# podule_2040.net
KiCad netlist of a schematic drawn in EAGLE
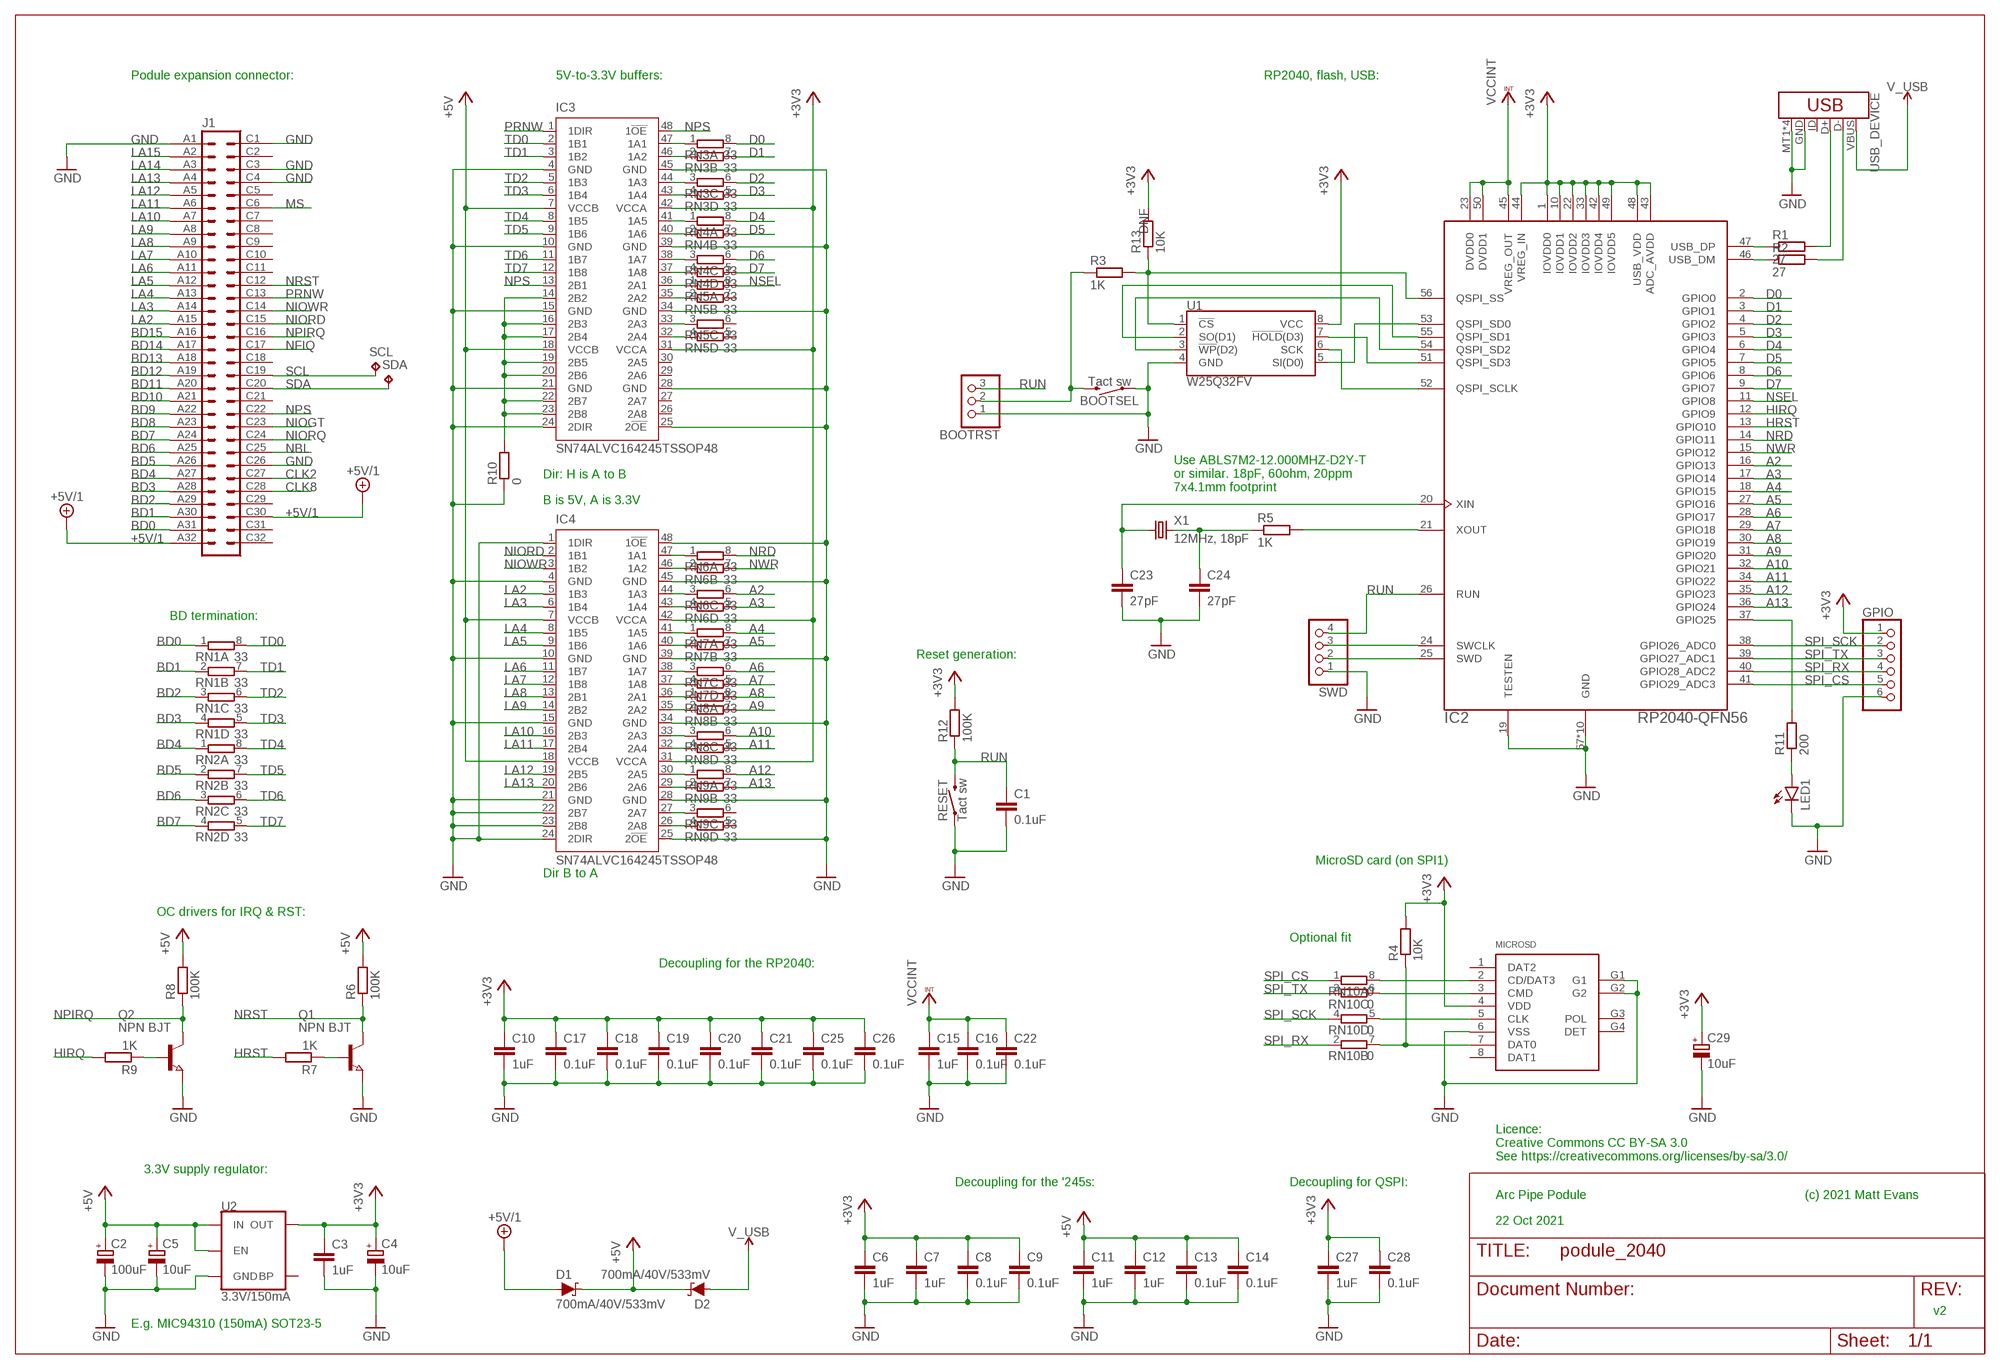
[diagram p0: schematic, sheet 1]

(export (version "E")
  (design (tool "Eeschema 10.0.6"))
  (components
    (comp (ref "BOOTRST")
      (value "PINHD-1X3")
      (footprint "eagle-import:1X03")
      (libsource (lib "eagle-import") (part "PINHD-1X3"))
    )
    (comp (ref "BOOTSEL")
      (value "Tact sw")
      (footprint "eagle-import:TACTILE_SWITCH_SMD_5.2MM")
      (libsource (lib "eagle-import") (part "MOMENTARY-SWITCH-SPST-SMD-5.2-REDUNDANT"))
    )
    (comp (ref "C1")
      (value "0.1uF")
      (footprint "eagle-import:C0603K")
      (libsource (lib "eagle-import") (part "C-EUC0603K"))
    )
    (comp (ref "C2")
      (value "100uF")
      (footprint "eagle-import:CT6032")
      (libsource (lib "eagle-import") (part "CPOL-EUCT6032"))
    )
    (comp (ref "C3")
      (value "1uF")
      (footprint "eagle-import:C0603K")
      (libsource (lib "eagle-import") (part "C-EUC0603K"))
    )
    (comp (ref "C4")
      (value "10uF")
      (footprint "eagle-import:A_3216-18W")
      (libsource (lib "eagle-import") (part "CPOL-EUA/3216-18W"))
    )
    (comp (ref "C5")
      (value "10uF")
      (footprint "eagle-import:A_3216-18W")
      (libsource (lib "eagle-import") (part "CPOL-EUA/3216-18W"))
    )
    (comp (ref "C6")
      (value "1uF")
      (footprint "eagle-import:C0603K")
      (libsource (lib "eagle-import") (part "C-EUC0603K"))
    )
    (comp (ref "C7")
      (value "1uF")
      (footprint "eagle-import:C0603K")
      (libsource (lib "eagle-import") (part "C-EUC0603K"))
    )
    (comp (ref "C8")
      (value "0.1uF")
      (footprint "eagle-import:C0603K")
      (libsource (lib "eagle-import") (part "C-EUC0603K"))
    )
    (comp (ref "C9")
      (value "0.1uF")
      (footprint "eagle-import:C0603K")
      (libsource (lib "eagle-import") (part "C-EUC0603K"))
    )
    (comp (ref "C10")
      (value "1uF")
      (footprint "eagle-import:C0603K")
      (libsource (lib "eagle-import") (part "C-EUC0603K"))
    )
    (comp (ref "C11")
      (value "1uF")
      (footprint "eagle-import:C0603K")
      (libsource (lib "eagle-import") (part "C-EUC0603K"))
    )
    (comp (ref "C12")
      (value "1uF")
      (footprint "eagle-import:C0603K")
      (libsource (lib "eagle-import") (part "C-EUC0603K"))
    )
    (comp (ref "C13")
      (value "0.1uF")
      (footprint "eagle-import:C0603K")
      (libsource (lib "eagle-import") (part "C-EUC0603K"))
    )
    (comp (ref "C14")
      (value "0.1uF")
      (footprint "eagle-import:C0603K")
      (libsource (lib "eagle-import") (part "C-EUC0603K"))
    )
    (comp (ref "C15")
      (value "1uF")
      (footprint "eagle-import:C0603K")
      (libsource (lib "eagle-import") (part "C-EUC0603K"))
    )
    (comp (ref "C16")
      (value "0.1uF")
      (footprint "eagle-import:C0603K")
      (libsource (lib "eagle-import") (part "C-EUC0603K"))
    )
    (comp (ref "C17")
      (value "0.1uF")
      (footprint "eagle-import:C0603K")
      (libsource (lib "eagle-import") (part "C-EUC0603K"))
    )
    (comp (ref "C18")
      (value "0.1uF")
      (footprint "eagle-import:C0603K")
      (libsource (lib "eagle-import") (part "C-EUC0603K"))
    )
    (comp (ref "C19")
      (value "0.1uF")
      (footprint "eagle-import:C0603K")
      (libsource (lib "eagle-import") (part "C-EUC0603K"))
    )
    (comp (ref "C20")
      (value "0.1uF")
      (footprint "eagle-import:C0603K")
      (libsource (lib "eagle-import") (part "C-EUC0603K"))
    )
    (comp (ref "C21")
      (value "0.1uF")
      (footprint "eagle-import:C0603K")
      (libsource (lib "eagle-import") (part "C-EUC0603K"))
    )
    (comp (ref "C22")
      (value "0.1uF")
      (footprint "eagle-import:C0603K")
      (libsource (lib "eagle-import") (part "C-EUC0603K"))
    )
    (comp (ref "C23")
      (value "27pF")
      (footprint "eagle-import:C0603K")
      (libsource (lib "eagle-import") (part "C-EUC0603K"))
    )
    (comp (ref "C24")
      (value "27pF")
      (footprint "eagle-import:C0603K")
      (libsource (lib "eagle-import") (part "C-EUC0603K"))
    )
    (comp (ref "C25")
      (value "0.1uF")
      (footprint "eagle-import:C0603K")
      (libsource (lib "eagle-import") (part "C-EUC0603K"))
    )
    (comp (ref "C26")
      (value "0.1uF")
      (footprint "eagle-import:C0603K")
      (libsource (lib "eagle-import") (part "C-EUC0603K"))
    )
    (comp (ref "C27")
      (value "1uF")
      (footprint "eagle-import:C0603K")
      (libsource (lib "eagle-import") (part "C-EUC0603K"))
    )
    (comp (ref "C28")
      (value "0.1uF")
      (footprint "eagle-import:C0603K")
      (libsource (lib "eagle-import") (part "C-EUC0603K"))
    )
    (comp (ref "C29")
      (value "10uF")
      (footprint "eagle-import:A_3216-18W")
      (libsource (lib "eagle-import") (part "CPOL-EUA/3216-18W"))
    )
    (comp (ref "D1")
      (value "700mA/40V/533mV")
      (footprint "eagle-import:SOT23-3")
      (libsource (lib "eagle-import") (part "DIODE-SCHOTTKY-ZLLS500"))
    )
    (comp (ref "D2")
      (value "700mA/40V/533mV")
      (footprint "eagle-import:SOT23-3")
      (libsource (lib "eagle-import") (part "DIODE-SCHOTTKY-ZLLS500"))
    )
    (comp (ref "GPIO")
      (value "PINHD-1X6")
      (footprint "eagle-import:1X06")
      (libsource (lib "eagle-import") (part "PINHD-1X6"))
    )
    (comp (ref "IC2")
      (value "RP2040-QFN56")
      (footprint "eagle-import:RP2040-QFN-56")
      (libsource (lib "eagle-import") (part "RP2040-QFN56"))
    )
    (comp (ref "IC3")
      (value "SN74ALVC164245TSSOP48")
      (footprint "eagle-import:TSSOP48")
      (libsource (lib "eagle-import") (part "SN74ALVC164245TSSOP48"))
    )
    (comp (ref "IC4")
      (value "SN74ALVC164245TSSOP48")
      (footprint "eagle-import:TSSOP48")
      (libsource (lib "eagle-import") (part "SN74ALVC164245TSSOP48"))
    )
    (comp (ref "J1")
      (value "VG64SHORT")
      (footprint "eagle-import:VG64KB-80MM")
      (libsource (lib "eagle-import") (part "VG64SHORT"))
    )
    (comp (ref "LED1")
      (value "LEDCHIPLED_1206")
      (footprint "eagle-import:CHIPLED_1206")
      (libsource (lib "eagle-import") (part "LEDCHIPLED_1206"))
    )
    (comp (ref "MICROSD")
      (value "MOLEX-USD-47309")
      (footprint "eagle-import:MOLEX-USD-47309")
      (libsource (lib "eagle-import") (part "MOLEX-USD-47309"))
    )
    (comp (ref "Q1")
      (value "NPN BJT")
      (footprint "eagle-import:SOT23")
      (libsource (lib "eagle-import") (part "NPN-TRANSISTOR_SOT23"))
    )
    (comp (ref "Q2")
      (value "NPN BJT")
      (footprint "eagle-import:SOT23")
      (libsource (lib "eagle-import") (part "NPN-TRANSISTOR_SOT23"))
    )
    (comp (ref "R1")
      (value "27")
      (footprint "eagle-import:R0805")
      (libsource (lib "eagle-import") (part "R-EU_R0805"))
    )
    (comp (ref "R2")
      (value "27")
      (footprint "eagle-import:R0805")
      (libsource (lib "eagle-import") (part "R-EU_R0805"))
    )
    (comp (ref "R3")
      (value "1K")
      (footprint "eagle-import:R0805")
      (libsource (lib "eagle-import") (part "R-EU_R0805"))
    )
    (comp (ref "R4")
      (value "10K")
      (footprint "eagle-import:R0805")
      (libsource (lib "eagle-import") (part "R-EU_R0805"))
    )
    (comp (ref "R5")
      (value "1K")
      (footprint "eagle-import:R0805")
      (libsource (lib "eagle-import") (part "R-EU_R0805"))
    )
    (comp (ref "R6")
      (value "100K")
      (footprint "eagle-import:R0805")
      (libsource (lib "eagle-import") (part "R-EU_R0805"))
    )
    (comp (ref "R7")
      (value "1K")
      (footprint "eagle-import:R0805")
      (libsource (lib "eagle-import") (part "R-EU_R0805"))
    )
    (comp (ref "R8")
      (value "100K")
      (footprint "eagle-import:R0805")
      (libsource (lib "eagle-import") (part "R-EU_R0805"))
    )
    (comp (ref "R9")
      (value "1K")
      (footprint "eagle-import:R0805")
      (libsource (lib "eagle-import") (part "R-EU_R0805"))
    )
    (comp (ref "R10")
      (value "0")
      (footprint "eagle-import:R0603")
      (libsource (lib "eagle-import") (part "R-EU_R0603"))
    )
    (comp (ref "R11")
      (value "200")
      (footprint "eagle-import:R0805")
      (libsource (lib "eagle-import") (part "R-EU_R0805"))
    )
    (comp (ref "R12")
      (value "100K")
      (footprint "eagle-import:R0805")
      (libsource (lib "eagle-import") (part "R-EU_R0805"))
    )
    (comp (ref "R13")
      (value "10K")
      (footprint "eagle-import:R0805")
      (libsource (lib "eagle-import") (part "R-EU_R0805"))
    )
    (comp (ref "RESET")
      (value "Tact sw")
      (footprint "eagle-import:TACTILE_SWITCH_SMD_5.2MM")
      (libsource (lib "eagle-import") (part "MOMENTARY-SWITCH-SPST-SMD-5.2-REDUNDANT"))
    )
    (comp (ref "RN1")
      (value "33")
      (footprint "eagle-import:0603-ARC")
      (libsource (lib "eagle-import") (part "4R-N0603-ARC"))
    )
    (comp (ref "RN2")
      (value "33")
      (footprint "eagle-import:0603-ARC")
      (libsource (lib "eagle-import") (part "4R-N0603-ARC"))
    )
    (comp (ref "RN3")
      (value "33")
      (footprint "eagle-import:0603-ARC")
      (libsource (lib "eagle-import") (part "4R-N0603-ARC"))
    )
    (comp (ref "RN4")
      (value "33")
      (footprint "eagle-import:0603-ARC")
      (libsource (lib "eagle-import") (part "4R-N0603-ARC"))
    )
    (comp (ref "RN5")
      (value "33")
      (footprint "eagle-import:0603-ARC")
      (libsource (lib "eagle-import") (part "4R-N0603-ARC"))
    )
    (comp (ref "RN6")
      (value "33")
      (footprint "eagle-import:0603-ARC")
      (libsource (lib "eagle-import") (part "4R-N0603-ARC"))
    )
    (comp (ref "RN7")
      (value "33")
      (footprint "eagle-import:0603-ARC")
      (libsource (lib "eagle-import") (part "4R-N0603-ARC"))
    )
    (comp (ref "RN8")
      (value "33")
      (footprint "eagle-import:0603-ARC")
      (libsource (lib "eagle-import") (part "4R-N0603-ARC"))
    )
    (comp (ref "RN9")
      (value "33")
      (footprint "eagle-import:0603-ARC")
      (libsource (lib "eagle-import") (part "4R-N0603-ARC"))
    )
    (comp (ref "RN10")
      (value "0")
      (footprint "eagle-import:0603-ARC")
      (libsource (lib "eagle-import") (part "4R-N0603-ARC"))
    )
    (comp (ref "SCL")
      (value "TPTP15R")
      (footprint "eagle-import:TP15R")
      (libsource (lib "eagle-import") (part "TPTP15R"))
    )
    (comp (ref "SDA")
      (value "TPTP15R")
      (footprint "eagle-import:TP15R")
      (libsource (lib "eagle-import") (part "TPTP15R"))
    )
    (comp (ref "SWD")
      (value "PINHD-1X4")
      (footprint "eagle-import:1X04")
      (libsource (lib "eagle-import") (part "PINHD-1X4"))
    )
    (comp (ref "U1")
      (value "W25Q32FV")
      (footprint "eagle-import:SOIC-8")
      (libsource (lib "eagle-import") (part "W25Q32FVSS"))
    )
    (comp (ref "U2")
      (value "3.3V/150mA")
      (footprint "eagle-import:SOT23-5")
      (libsource (lib "eagle-import") (part "V_REG_MIC52053.3V"))
    )
    (comp (ref "USB_DEVICE")
      (value "USB_MICRO-B_SMT")
      (footprint "eagle-import:USB-MICROB")
      (libsource (lib "eagle-import") (part "USB_MICRO-B_SMT"))
    )
    (comp (ref "X1")
      (value "12MHz, 18pF")
      (footprint "eagle-import:7.5X5-2-PAD")
      (libsource (lib "eagle-import") (part "CRYSTALS-NOGND-12SMX-A"))
    )
  )
  (nets
    (net (code "1") (name "+3V3") (class "Default")
      (node (ref "C10") (pin "1") (pinfunction "1_1") (pintype "passive"))
      (node (ref "C17") (pin "1") (pinfunction "1_1") (pintype "passive"))
      (node (ref "C18") (pin "1") (pinfunction "1_1") (pintype "passive"))
      (node (ref "C19") (pin "1") (pinfunction "1_1") (pintype "passive"))
      (node (ref "C20") (pin "1") (pinfunction "1_1") (pintype "passive"))
      (node (ref "C21") (pin "1") (pinfunction "1_1") (pintype "passive"))
      (node (ref "C25") (pin "1") (pinfunction "1_1") (pintype "passive"))
      (node (ref "C26") (pin "1") (pinfunction "1_1") (pintype "passive"))
      (node (ref "C27") (pin "1") (pinfunction "1_1") (pintype "passive"))
      (node (ref "C28") (pin "1") (pinfunction "1_1") (pintype "passive"))
      (node (ref "C29") (pin "+") (pinfunction "+_+") (pintype "passive"))
      (node (ref "C3") (pin "1") (pinfunction "1_1") (pintype "passive"))
      (node (ref "C4") (pin "+") (pinfunction "+_+") (pintype "passive"))
      (node (ref "C6") (pin "1") (pinfunction "1_1") (pintype "passive"))
      (node (ref "C7") (pin "1") (pinfunction "1_1") (pintype "passive"))
      (node (ref "C8") (pin "1") (pinfunction "1_1") (pintype "passive"))
      (node (ref "C9") (pin "1") (pinfunction "1_1") (pintype "passive"))
      (node (ref "GPIO") (pin "1") (pinfunction "1_1") (pintype "passive"))
      (node (ref "IC2") (pin "1") (pinfunction "IOVDD0_1") (pintype "power_in"))
      (node (ref "IC2") (pin "10") (pinfunction "IOVDD1_10") (pintype "power_in"))
      (node (ref "IC2") (pin "22") (pinfunction "IOVDD2_22") (pintype "power_in"))
      (node (ref "IC2") (pin "33") (pinfunction "IOVDD3_33") (pintype "power_in"))
      (node (ref "IC2") (pin "42") (pinfunction "IOVDD4_42") (pintype "power_in"))
      (node (ref "IC2") (pin "43") (pinfunction "ADC_AVDD_43") (pintype "power_in"))
      (node (ref "IC2") (pin "44") (pinfunction "VREG_IN_44") (pintype "power_in"))
      (node (ref "IC2") (pin "48") (pinfunction "USB_VDD_48") (pintype "power_in"))
      (node (ref "IC2") (pin "49") (pinfunction "IOVDD5_49") (pintype "power_in"))
      (node (ref "IC3") (pin "31") (pinfunction "VCCA_31") (pintype "power_in"))
      (node (ref "IC3") (pin "42") (pinfunction "VCCA_42") (pintype "power_in"))
      (node (ref "IC4") (pin "31") (pinfunction "VCCA_31") (pintype "power_in"))
      (node (ref "IC4") (pin "42") (pinfunction "VCCA_42") (pintype "power_in"))
      (node (ref "MICROSD") (pin "4") (pinfunction "VDD_4") (pintype "bidirectional"))
      (node (ref "R12") (pin "2") (pinfunction "2_2") (pintype "passive"))
      (node (ref "R13") (pin "2") (pinfunction "2_2") (pintype "passive"))
      (node (ref "R4") (pin "2") (pinfunction "2_2") (pintype "passive"))
      (node (ref "U1") (pin "8") (pinfunction "VCC_8") (pintype "bidirectional"))
      (node (ref "U2") (pin "5") (pinfunction "OUT_5") (pintype "passive"))
    )
    (net (code "2") (name "+5V") (class "Default")
      (node (ref "C11") (pin "1") (pinfunction "1_1") (pintype "passive"))
      (node (ref "C12") (pin "1") (pinfunction "1_1") (pintype "passive"))
      (node (ref "C13") (pin "1") (pinfunction "1_1") (pintype "passive"))
      (node (ref "C14") (pin "1") (pinfunction "1_1") (pintype "passive"))
      (node (ref "C2") (pin "+") (pinfunction "+_+") (pintype "passive"))
      (node (ref "C5") (pin "+") (pinfunction "+_+") (pintype "passive"))
      (node (ref "D1") (pin "3") (pinfunction "C_3") (pintype "passive"))
      (node (ref "D2") (pin "3") (pinfunction "C_3") (pintype "passive"))
      (node (ref "IC3") (pin "18") (pinfunction "VCCB_18") (pintype "power_in"))
      (node (ref "IC3") (pin "7") (pinfunction "VCCB_7") (pintype "power_in"))
      (node (ref "IC4") (pin "18") (pinfunction "VCCB_18") (pintype "power_in"))
      (node (ref "IC4") (pin "7") (pinfunction "VCCB_7") (pintype "power_in"))
      (node (ref "R6") (pin "2") (pinfunction "2_2") (pintype "passive"))
      (node (ref "R8") (pin "2") (pinfunction "2_2") (pintype "passive"))
      (node (ref "U2") (pin "1") (pinfunction "IN_1") (pintype "input"))
      (node (ref "U2") (pin "3") (pinfunction "EN_3") (pintype "input"))
    )
    (net (code "3") (name "+5V{slash}1") (class "Default")
      (node (ref "D1") (pin "1") (pinfunction "A_1") (pintype "passive"))
      (node (ref "J1") (pin "A32") (pinfunction "A32_A32") (pintype "passive"))
      (node (ref "J1") (pin "C30") (pinfunction "C30_C30") (pintype "passive"))
    )
    (net (code "4") (name "/A2") (class "Default")
      (node (ref "IC2") (pin "16") (pinfunction "GPIO13_16") (pintype "bidirectional"))
      (node (ref "RN6") (pin "6") (pinfunction "2_6") (pintype "passive"))
    )
    (net (code "5") (name "/A3") (class "Default")
      (node (ref "IC2") (pin "17") (pinfunction "GPIO14_17") (pintype "bidirectional"))
      (node (ref "RN6") (pin "5") (pinfunction "2_5") (pintype "passive"))
    )
    (net (code "6") (name "/A4") (class "Default")
      (node (ref "IC2") (pin "18") (pinfunction "GPIO15_18") (pintype "bidirectional"))
      (node (ref "RN7") (pin "8") (pinfunction "2_8") (pintype "passive"))
    )
    (net (code "7") (name "/A5") (class "Default")
      (node (ref "IC2") (pin "27") (pinfunction "GPIO16_27") (pintype "bidirectional"))
      (node (ref "RN7") (pin "7") (pinfunction "2_7") (pintype "passive"))
    )
    (net (code "8") (name "/A6") (class "Default")
      (node (ref "IC2") (pin "28") (pinfunction "GPIO17_28") (pintype "bidirectional"))
      (node (ref "RN7") (pin "6") (pinfunction "2_6") (pintype "passive"))
    )
    (net (code "9") (name "/A7") (class "Default")
      (node (ref "IC2") (pin "29") (pinfunction "GPIO18_29") (pintype "bidirectional"))
      (node (ref "RN7") (pin "5") (pinfunction "2_5") (pintype "passive"))
    )
    (net (code "10") (name "/A8") (class "Default")
      (node (ref "IC2") (pin "30") (pinfunction "GPIO19_30") (pintype "bidirectional"))
      (node (ref "RN8") (pin "8") (pinfunction "2_8") (pintype "passive"))
    )
    (net (code "11") (name "/A9") (class "Default")
      (node (ref "IC2") (pin "31") (pinfunction "GPIO20_31") (pintype "bidirectional"))
      (node (ref "RN8") (pin "7") (pinfunction "2_7") (pintype "passive"))
    )
    (net (code "12") (name "/A10") (class "Default")
      (node (ref "IC2") (pin "32") (pinfunction "GPIO21_32") (pintype "bidirectional"))
      (node (ref "RN8") (pin "6") (pinfunction "2_6") (pintype "passive"))
    )
    (net (code "13") (name "/A11") (class "Default")
      (node (ref "IC2") (pin "34") (pinfunction "GPIO22_34") (pintype "bidirectional"))
      (node (ref "RN8") (pin "5") (pinfunction "2_5") (pintype "passive"))
    )
    (net (code "14") (name "/A12") (class "Default")
      (node (ref "IC2") (pin "35") (pinfunction "GPIO23_35") (pintype "bidirectional"))
      (node (ref "RN9") (pin "8") (pinfunction "2_8") (pintype "passive"))
    )
    (net (code "15") (name "/A13") (class "Default")
      (node (ref "IC2") (pin "36") (pinfunction "GPIO24_36") (pintype "bidirectional"))
      (node (ref "RN9") (pin "7") (pinfunction "2_7") (pintype "passive"))
    )
    (net (code "16") (name "/BD0") (class "Default")
      (node (ref "J1") (pin "A31") (pinfunction "A31_A31") (pintype "passive"))
      (node (ref "RN1") (pin "1") (pinfunction "1_1") (pintype "passive"))
    )
    (net (code "17") (name "/BD1") (class "Default")
      (node (ref "J1") (pin "A30") (pinfunction "A30_A30") (pintype "passive"))
      (node (ref "RN1") (pin "2") (pinfunction "1_2") (pintype "passive"))
    )
    (net (code "18") (name "/BD2") (class "Default")
      (node (ref "J1") (pin "A29") (pinfunction "A29_A29") (pintype "passive"))
      (node (ref "RN1") (pin "3") (pinfunction "1_3") (pintype "passive"))
    )
    (net (code "19") (name "/BD3") (class "Default")
      (node (ref "J1") (pin "A28") (pinfunction "A28_A28") (pintype "passive"))
      (node (ref "RN1") (pin "4") (pinfunction "1_4") (pintype "passive"))
    )
    (net (code "20") (name "/BD4") (class "Default")
      (node (ref "J1") (pin "A27") (pinfunction "A27_A27") (pintype "passive"))
      (node (ref "RN2") (pin "1") (pinfunction "1_1") (pintype "passive"))
    )
    (net (code "21") (name "/BD5") (class "Default")
      (node (ref "J1") (pin "A26") (pinfunction "A26_A26") (pintype "passive"))
      (node (ref "RN2") (pin "2") (pinfunction "1_2") (pintype "passive"))
    )
    (net (code "22") (name "/BD6") (class "Default")
      (node (ref "J1") (pin "A25") (pinfunction "A25_A25") (pintype "passive"))
      (node (ref "RN2") (pin "3") (pinfunction "1_3") (pintype "passive"))
    )
    (net (code "23") (name "/BD7") (class "Default")
      (node (ref "J1") (pin "A24") (pinfunction "A24_A24") (pintype "passive"))
      (node (ref "RN2") (pin "4") (pinfunction "1_4") (pintype "passive"))
    )
    (net (code "24") (name "/BD8") (class "Default")
      (node (ref "J1") (pin "A23") (pinfunction "A23_A23") (pintype "passive"))
    )
    (net (code "25") (name "/BD9") (class "Default")
      (node (ref "J1") (pin "A22") (pinfunction "A22_A22") (pintype "passive"))
    )
    (net (code "26") (name "/BD10") (class "Default")
      (node (ref "J1") (pin "A21") (pinfunction "A21_A21") (pintype "passive"))
    )
    (net (code "27") (name "/BD11") (class "Default")
      (node (ref "J1") (pin "A20") (pinfunction "A20_A20") (pintype "passive"))
    )
    (net (code "28") (name "/BD12") (class "Default")
      (node (ref "J1") (pin "A19") (pinfunction "A19_A19") (pintype "passive"))
    )
    (net (code "29") (name "/BD13") (class "Default")
      (node (ref "J1") (pin "A18") (pinfunction "A18_A18") (pintype "passive"))
    )
    (net (code "30") (name "/BD14") (class "Default")
      (node (ref "J1") (pin "A17") (pinfunction "A17_A17") (pintype "passive"))
    )
    (net (code "31") (name "/BD15") (class "Default")
      (node (ref "J1") (pin "A16") (pinfunction "A16_A16") (pintype "passive"))
    )
    (net (code "32") (name "/CLK2") (class "Default")
      (node (ref "J1") (pin "C27") (pinfunction "C27_C27") (pintype "passive"))
    )
    (net (code "33") (name "/CLK8") (class "Default")
      (node (ref "J1") (pin "C28") (pinfunction "C28_C28") (pintype "passive"))
    )
    (net (code "34") (name "/D0") (class "Default")
      (node (ref "IC2") (pin "2") (pinfunction "GPIO0_2") (pintype "bidirectional"))
      (node (ref "RN3") (pin "8") (pinfunction "2_8") (pintype "passive"))
    )
    (net (code "35") (name "/D1") (class "Default")
      (node (ref "IC2") (pin "3") (pinfunction "GPIO1_3") (pintype "bidirectional"))
      (node (ref "RN3") (pin "7") (pinfunction "2_7") (pintype "passive"))
    )
    (net (code "36") (name "/D2") (class "Default")
      (node (ref "IC2") (pin "4") (pinfunction "GPIO2_4") (pintype "bidirectional"))
      (node (ref "RN3") (pin "6") (pinfunction "2_6") (pintype "passive"))
    )
    (net (code "37") (name "/D3") (class "Default")
      (node (ref "IC2") (pin "5") (pinfunction "GPIO3_5") (pintype "bidirectional"))
      (node (ref "RN3") (pin "5") (pinfunction "2_5") (pintype "passive"))
    )
    (net (code "38") (name "/D4") (class "Default")
      (node (ref "IC2") (pin "6") (pinfunction "GPIO4_6") (pintype "bidirectional"))
      (node (ref "RN4") (pin "8") (pinfunction "2_8") (pintype "passive"))
    )
    (net (code "39") (name "/D5") (class "Default")
      (node (ref "IC2") (pin "7") (pinfunction "GPIO5_7") (pintype "bidirectional"))
      (node (ref "RN4") (pin "7") (pinfunction "2_7") (pintype "passive"))
    )
    (net (code "40") (name "/D6") (class "Default")
      (node (ref "IC2") (pin "8") (pinfunction "GPIO6_8") (pintype "bidirectional"))
      (node (ref "RN4") (pin "6") (pinfunction "2_6") (pintype "passive"))
    )
    (net (code "41") (name "/D7") (class "Default")
      (node (ref "IC2") (pin "9") (pinfunction "GPIO7_9") (pintype "bidirectional"))
      (node (ref "RN4") (pin "5") (pinfunction "2_5") (pintype "passive"))
    )
    (net (code "42") (name "/HIRQ") (class "Default")
      (node (ref "IC2") (pin "12") (pinfunction "GPIO9_12") (pintype "bidirectional"))
      (node (ref "R9") (pin "2") (pinfunction "2_2") (pintype "passive"))
    )
    (net (code "43") (name "/HRST") (class "Default")
      (node (ref "IC2") (pin "13") (pinfunction "GPIO10_13") (pintype "bidirectional"))
      (node (ref "R7") (pin "2") (pinfunction "2_2") (pintype "passive"))
    )
    (net (code "44") (name "/LA2") (class "Default")
      (node (ref "IC4") (pin "5") (pinfunction "1B3_5") (pintype "tri_state"))
      (node (ref "J1") (pin "A15") (pinfunction "A15_A15") (pintype "passive"))
    )
    (net (code "45") (name "/LA3") (class "Default")
      (node (ref "IC4") (pin "6") (pinfunction "1B4_6") (pintype "tri_state"))
      (node (ref "J1") (pin "A14") (pinfunction "A14_A14") (pintype "passive"))
    )
    (net (code "46") (name "/LA4") (class "Default")
      (node (ref "IC4") (pin "8") (pinfunction "1B5_8") (pintype "tri_state"))
      (node (ref "J1") (pin "A13") (pinfunction "A13_A13") (pintype "passive"))
    )
    (net (code "47") (name "/LA5") (class "Default")
      (node (ref "IC4") (pin "9") (pinfunction "1B6_9") (pintype "tri_state"))
      (node (ref "J1") (pin "A12") (pinfunction "A12_A12") (pintype "passive"))
    )
    (net (code "48") (name "/LA6") (class "Default")
      (node (ref "IC4") (pin "11") (pinfunction "1B7_11") (pintype "tri_state"))
      (node (ref "J1") (pin "A11") (pinfunction "A11_A11") (pintype "passive"))
    )
    (net (code "49") (name "/LA7") (class "Default")
      (node (ref "IC4") (pin "12") (pinfunction "1B8_12") (pintype "tri_state"))
      (node (ref "J1") (pin "A10") (pinfunction "A10_A10") (pintype "passive"))
    )
    (net (code "50") (name "/LA8") (class "Default")
      (node (ref "IC4") (pin "13") (pinfunction "2B1_13") (pintype "tri_state"))
      (node (ref "J1") (pin "A9") (pinfunction "A9_A9") (pintype "passive"))
    )
    (net (code "51") (name "/LA9") (class "Default")
      (node (ref "IC4") (pin "14") (pinfunction "2B2_14") (pintype "tri_state"))
      (node (ref "J1") (pin "A8") (pinfunction "A8_A8") (pintype "passive"))
    )
    (net (code "52") (name "/LA10") (class "Default")
      (node (ref "IC4") (pin "16") (pinfunction "2B3_16") (pintype "tri_state"))
      (node (ref "J1") (pin "A7") (pinfunction "A7_A7") (pintype "passive"))
    )
    (net (code "53") (name "/LA11") (class "Default")
      (node (ref "IC4") (pin "17") (pinfunction "2B4_17") (pintype "tri_state"))
      (node (ref "J1") (pin "A6") (pinfunction "A6_A6") (pintype "passive"))
    )
    (net (code "54") (name "/LA12") (class "Default")
      (node (ref "IC4") (pin "19") (pinfunction "2B5_19") (pintype "tri_state"))
      (node (ref "J1") (pin "A5") (pinfunction "A5_A5") (pintype "passive"))
    )
    (net (code "55") (name "/LA13") (class "Default")
      (node (ref "IC4") (pin "20") (pinfunction "2B6_20") (pintype "tri_state"))
      (node (ref "J1") (pin "A4") (pinfunction "A4_A4") (pintype "passive"))
    )
    (net (code "56") (name "/LA14") (class "Default")
      (node (ref "J1") (pin "A3") (pinfunction "A3_A3") (pintype "passive"))
    )
    (net (code "57") (name "/LA15") (class "Default")
      (node (ref "J1") (pin "A2") (pinfunction "A2_A2") (pintype "passive"))
    )
    (net (code "58") (name "/MS") (class "Default")
      (node (ref "J1") (pin "C6") (pinfunction "C6_C6") (pintype "passive"))
    )
    (net (code "59") (name "/NBL") (class "Default")
      (node (ref "J1") (pin "C25") (pinfunction "C25_C25") (pintype "passive"))
    )
    (net (code "60") (name "/NFIQ") (class "Default")
      (node (ref "J1") (pin "C17") (pinfunction "C17_C17") (pintype "passive"))
    )
    (net (code "61") (name "/NIOGT") (class "Default")
      (node (ref "J1") (pin "C23") (pinfunction "C23_C23") (pintype "passive"))
    )
    (net (code "62") (name "/NIORD") (class "Default")
      (node (ref "IC4") (pin "2") (pinfunction "1B1_2") (pintype "tri_state"))
      (node (ref "J1") (pin "C15") (pinfunction "C15_C15") (pintype "passive"))
    )
    (net (code "63") (name "/NIORQ") (class "Default")
      (node (ref "J1") (pin "C24") (pinfunction "C24_C24") (pintype "passive"))
    )
    (net (code "64") (name "/NIOWR") (class "Default")
      (node (ref "IC4") (pin "3") (pinfunction "1B2_3") (pintype "tri_state"))
      (node (ref "J1") (pin "C14") (pinfunction "C14_C14") (pintype "passive"))
    )
    (net (code "65") (name "/NPIRQ") (class "Default")
      (node (ref "J1") (pin "C16") (pinfunction "C16_C16") (pintype "passive"))
      (node (ref "Q2") (pin "3") (pinfunction "C_3") (pintype "passive"))
      (node (ref "R8") (pin "1") (pinfunction "1_1") (pintype "passive"))
    )
    (net (code "66") (name "/NPS") (class "Default")
      (node (ref "IC3") (pin "13") (pinfunction "2B1_13") (pintype "tri_state"))
      (node (ref "IC3") (pin "48") (pinfunction "1~{OE}_48") (pintype "input"))
      (node (ref "J1") (pin "C22") (pinfunction "C22_C22") (pintype "passive"))
    )
    (net (code "67") (name "/NRD") (class "Default")
      (node (ref "IC2") (pin "14") (pinfunction "GPIO11_14") (pintype "bidirectional"))
      (node (ref "RN6") (pin "8") (pinfunction "2_8") (pintype "passive"))
    )
    (net (code "68") (name "/NRST") (class "Default")
      (node (ref "J1") (pin "C12") (pinfunction "C12_C12") (pintype "passive"))
      (node (ref "Q1") (pin "3") (pinfunction "C_3") (pintype "passive"))
      (node (ref "R6") (pin "1") (pinfunction "1_1") (pintype "passive"))
    )
    (net (code "69") (name "/NSEL") (class "Default")
      (node (ref "IC2") (pin "11") (pinfunction "GPIO8_11") (pintype "bidirectional"))
      (node (ref "RN5") (pin "8") (pinfunction "2_8") (pintype "passive"))
    )
    (net (code "70") (name "/NWR") (class "Default")
      (node (ref "IC2") (pin "15") (pinfunction "GPIO12_15") (pintype "bidirectional"))
      (node (ref "RN6") (pin "7") (pinfunction "2_7") (pintype "passive"))
    )
    (net (code "71") (name "/PRNW") (class "Default")
      (node (ref "IC3") (pin "1") (pinfunction "1DIR_1") (pintype "input"))
      (node (ref "J1") (pin "C13") (pinfunction "C13_C13") (pintype "passive"))
    )
    (net (code "72") (name "/RUN") (class "Default")
      (node (ref "BOOTRST") (pin "3") (pinfunction "3_3") (pintype "passive"))
      (node (ref "C1") (pin "1") (pinfunction "1_1") (pintype "passive"))
      (node (ref "IC2") (pin "26") (pinfunction "RUN_26") (pintype "input"))
      (node (ref "R12") (pin "1") (pinfunction "1_1") (pintype "passive"))
      (node (ref "RESET") (pin "3") (pinfunction "2_3") (pintype "passive"))
      (node (ref "RESET") (pin "4") (pinfunction "2_4") (pintype "passive"))
      (node (ref "SWD") (pin "4") (pinfunction "4_4") (pintype "passive"))
    )
    (net (code "73") (name "/SCL") (class "Default")
      (node (ref "J1") (pin "C19") (pinfunction "C19_C19") (pintype "passive"))
      (node (ref "SCL") (pin "TP") (pinfunction "TP_TP") (pintype "input"))
    )
    (net (code "74") (name "/SDA") (class "Default")
      (node (ref "J1") (pin "C20") (pinfunction "C20_C20") (pintype "passive"))
      (node (ref "SDA") (pin "TP") (pinfunction "TP_TP") (pintype "input"))
    )
    (net (code "75") (name "/SPI_CS") (class "Default")
      (node (ref "GPIO") (pin "5") (pinfunction "5_5") (pintype "passive"))
      (node (ref "IC2") (pin "41") (pinfunction "GPIO29_ADC3_41") (pintype "bidirectional"))
      (node (ref "RN10") (pin "1") (pinfunction "1_1") (pintype "passive"))
    )
    (net (code "76") (name "/SPI_RX") (class "Default")
      (node (ref "GPIO") (pin "4") (pinfunction "4_4") (pintype "passive"))
      (node (ref "IC2") (pin "40") (pinfunction "GPIO28_ADC2_40") (pintype "bidirectional"))
      (node (ref "RN10") (pin "2") (pinfunction "1_2") (pintype "passive"))
    )
    (net (code "77") (name "/SPI_SCK") (class "Default")
      (node (ref "GPIO") (pin "2") (pinfunction "2_2") (pintype "passive"))
      (node (ref "IC2") (pin "38") (pinfunction "GPIO26_ADC0_38") (pintype "bidirectional"))
      (node (ref "RN10") (pin "4") (pinfunction "1_4") (pintype "passive"))
    )
    (net (code "78") (name "/SPI_TX") (class "Default")
      (node (ref "GPIO") (pin "3") (pinfunction "3_3") (pintype "passive"))
      (node (ref "IC2") (pin "39") (pinfunction "GPIO27_ADC1_39") (pintype "bidirectional"))
      (node (ref "RN10") (pin "3") (pinfunction "1_3") (pintype "passive"))
    )
    (net (code "79") (name "/TD0") (class "Default")
      (node (ref "IC3") (pin "2") (pinfunction "1B1_2") (pintype "tri_state"))
      (node (ref "RN1") (pin "8") (pinfunction "2_8") (pintype "passive"))
    )
    (net (code "80") (name "/TD1") (class "Default")
      (node (ref "IC3") (pin "3") (pinfunction "1B2_3") (pintype "tri_state"))
      (node (ref "RN1") (pin "7") (pinfunction "2_7") (pintype "passive"))
    )
    (net (code "81") (name "/TD2") (class "Default")
      (node (ref "IC3") (pin "5") (pinfunction "1B3_5") (pintype "tri_state"))
      (node (ref "RN1") (pin "6") (pinfunction "2_6") (pintype "passive"))
    )
    (net (code "82") (name "/TD3") (class "Default")
      (node (ref "IC3") (pin "6") (pinfunction "1B4_6") (pintype "tri_state"))
      (node (ref "RN1") (pin "5") (pinfunction "2_5") (pintype "passive"))
    )
    (net (code "83") (name "/TD4") (class "Default")
      (node (ref "IC3") (pin "8") (pinfunction "1B5_8") (pintype "tri_state"))
      (node (ref "RN2") (pin "8") (pinfunction "2_8") (pintype "passive"))
    )
    (net (code "84") (name "/TD5") (class "Default")
      (node (ref "IC3") (pin "9") (pinfunction "1B6_9") (pintype "tri_state"))
      (node (ref "RN2") (pin "7") (pinfunction "2_7") (pintype "passive"))
    )
    (net (code "85") (name "/TD6") (class "Default")
      (node (ref "IC3") (pin "11") (pinfunction "1B7_11") (pintype "tri_state"))
      (node (ref "RN2") (pin "6") (pinfunction "2_6") (pintype "passive"))
    )
    (net (code "86") (name "/TD7") (class "Default")
      (node (ref "IC3") (pin "12") (pinfunction "1B8_12") (pintype "tri_state"))
      (node (ref "RN2") (pin "5") (pinfunction "2_5") (pintype "passive"))
    )
    (net (code "87") (name "GND") (class "Default")
      (node (ref "BOOTRST") (pin "1") (pinfunction "1_1") (pintype "passive"))
      (node (ref "BOOTSEL") (pin "1") (pinfunction "1_1") (pintype "passive"))
      (node (ref "BOOTSEL") (pin "2") (pinfunction "1_2") (pintype "passive"))
      (node (ref "C1") (pin "2") (pinfunction "2_2") (pintype "passive"))
      (node (ref "C10") (pin "2") (pinfunction "2_2") (pintype "passive"))
      (node (ref "C11") (pin "2") (pinfunction "2_2") (pintype "passive"))
      (node (ref "C12") (pin "2") (pinfunction "2_2") (pintype "passive"))
      (node (ref "C13") (pin "2") (pinfunction "2_2") (pintype "passive"))
      (node (ref "C14") (pin "2") (pinfunction "2_2") (pintype "passive"))
      (node (ref "C15") (pin "2") (pinfunction "2_2") (pintype "passive"))
      (node (ref "C16") (pin "2") (pinfunction "2_2") (pintype "passive"))
      (node (ref "C17") (pin "2") (pinfunction "2_2") (pintype "passive"))
      (node (ref "C18") (pin "2") (pinfunction "2_2") (pintype "passive"))
      (node (ref "C19") (pin "2") (pinfunction "2_2") (pintype "passive"))
      (node (ref "C2") (pin "-") (pinfunction "-_-") (pintype "passive"))
      (node (ref "C20") (pin "2") (pinfunction "2_2") (pintype "passive"))
      (node (ref "C21") (pin "2") (pinfunction "2_2") (pintype "passive"))
      (node (ref "C22") (pin "2") (pinfunction "2_2") (pintype "passive"))
      (node (ref "C23") (pin "2") (pinfunction "2_2") (pintype "passive"))
      (node (ref "C24") (pin "2") (pinfunction "2_2") (pintype "passive"))
      (node (ref "C25") (pin "2") (pinfunction "2_2") (pintype "passive"))
      (node (ref "C26") (pin "2") (pinfunction "2_2") (pintype "passive"))
      (node (ref "C27") (pin "2") (pinfunction "2_2") (pintype "passive"))
      (node (ref "C28") (pin "2") (pinfunction "2_2") (pintype "passive"))
      (node (ref "C29") (pin "-") (pinfunction "-_-") (pintype "passive"))
      (node (ref "C3") (pin "2") (pinfunction "2_2") (pintype "passive"))
      (node (ref "C4") (pin "-") (pinfunction "-_-") (pintype "passive"))
      (node (ref "C5") (pin "-") (pinfunction "-_-") (pintype "passive"))
      (node (ref "C6") (pin "2") (pinfunction "2_2") (pintype "passive"))
      (node (ref "C7") (pin "2") (pinfunction "2_2") (pintype "passive"))
      (node (ref "C8") (pin "2") (pinfunction "2_2") (pintype "passive"))
      (node (ref "C9") (pin "2") (pinfunction "2_2") (pintype "passive"))
      (node (ref "GPIO") (pin "6") (pinfunction "6_6") (pintype "passive"))
      (node (ref "IC2") (pin "19") (pinfunction "TESTEN_19") (pintype "passive"))
      (node (ref "IC2") (pin "57") (pinfunction "GND_57") (pintype "power_in"))
      (node (ref "IC2") (pin "58") (pinfunction "GND_58") (pintype "power_in"))
      (node (ref "IC2") (pin "59") (pinfunction "GND_59") (pintype "power_in"))
      (node (ref "IC2") (pin "60") (pinfunction "GND_60") (pintype "power_in"))
      (node (ref "IC2") (pin "61") (pinfunction "GND_61") (pintype "power_in"))
      (node (ref "IC2") (pin "62") (pinfunction "GND_62") (pintype "power_in"))
      (node (ref "IC2") (pin "63") (pinfunction "GND_63") (pintype "power_in"))
      (node (ref "IC2") (pin "64") (pinfunction "GND_64") (pintype "power_in"))
      (node (ref "IC2") (pin "65") (pinfunction "GND_65") (pintype "power_in"))
      (node (ref "IC2") (pin "66") (pinfunction "GND_66") (pintype "power_in"))
      (node (ref "IC3") (pin "10") (pinfunction "GND_10") (pintype "power_in"))
      (node (ref "IC3") (pin "15") (pinfunction "GND_15") (pintype "power_in"))
      (node (ref "IC3") (pin "21") (pinfunction "GND_21") (pintype "tri_state"))
      (node (ref "IC3") (pin "24") (pinfunction "2DIR_24") (pintype "input"))
      (node (ref "IC3") (pin "25") (pinfunction "2~{OE}_25") (pintype "input"))
      (node (ref "IC3") (pin "28") (pinfunction "GND_28") (pintype "power_in"))
      (node (ref "IC3") (pin "34") (pinfunction "GND_34") (pintype "power_in"))
      (node (ref "IC3") (pin "39") (pinfunction "GND_39") (pintype "tri_state"))
      (node (ref "IC3") (pin "4") (pinfunction "GND_4") (pintype "power_in"))
      (node (ref "IC3") (pin "45") (pinfunction "GND_45") (pintype "power_in"))
      (node (ref "IC4") (pin "1") (pinfunction "1DIR_1") (pintype "input"))
      (node (ref "IC4") (pin "10") (pinfunction "GND_10") (pintype "power_in"))
      (node (ref "IC4") (pin "15") (pinfunction "GND_15") (pintype "power_in"))
      (node (ref "IC4") (pin "21") (pinfunction "GND_21") (pintype "tri_state"))
      (node (ref "IC4") (pin "22") (pinfunction "2B7_22") (pintype "tri_state"))
      (node (ref "IC4") (pin "23") (pinfunction "2B8_23") (pintype "tri_state"))
      (node (ref "IC4") (pin "24") (pinfunction "2DIR_24") (pintype "input"))
      (node (ref "IC4") (pin "25") (pinfunction "2~{OE}_25") (pintype "input"))
      (node (ref "IC4") (pin "28") (pinfunction "GND_28") (pintype "power_in"))
      (node (ref "IC4") (pin "34") (pinfunction "GND_34") (pintype "power_in"))
      (node (ref "IC4") (pin "39") (pinfunction "GND_39") (pintype "tri_state"))
      (node (ref "IC4") (pin "4") (pinfunction "GND_4") (pintype "power_in"))
      (node (ref "IC4") (pin "45") (pinfunction "GND_45") (pintype "power_in"))
      (node (ref "IC4") (pin "48") (pinfunction "1~{OE}_48") (pintype "input"))
      (node (ref "J1") (pin "A1") (pinfunction "A1_A1") (pintype "passive"))
      (node (ref "J1") (pin "C1") (pinfunction "C1_C1") (pintype "passive"))
      (node (ref "J1") (pin "C26") (pinfunction "C26_C26") (pintype "passive"))
      (node (ref "J1") (pin "C3") (pinfunction "C3_C3") (pintype "passive"))
      (node (ref "J1") (pin "C4") (pinfunction "C4_C4") (pintype "passive"))
      (node (ref "LED1") (pin "C") (pinfunction "C_C") (pintype "passive"))
      (node (ref "MICROSD") (pin "6") (pinfunction "VSS_6") (pintype "bidirectional"))
      (node (ref "MICROSD") (pin "G1") (pinfunction "G1_G1") (pintype "bidirectional"))
      (node (ref "MICROSD") (pin "G2") (pinfunction "G2_G2") (pintype "bidirectional"))
      (node (ref "Q1") (pin "2") (pinfunction "E_2") (pintype "passive"))
      (node (ref "Q2") (pin "2") (pinfunction "E_2") (pintype "passive"))
      (node (ref "R10") (pin "1") (pinfunction "1_1") (pintype "passive"))
      (node (ref "RESET") (pin "1") (pinfunction "1_1") (pintype "passive"))
      (node (ref "RESET") (pin "2") (pinfunction "1_2") (pintype "passive"))
      (node (ref "SWD") (pin "1") (pinfunction "1_1") (pintype "passive"))
      (node (ref "U1") (pin "4") (pinfunction "GND_4") (pintype "bidirectional"))
      (node (ref "U2") (pin "2") (pinfunction "GND_2") (pintype "input"))
      (node (ref "USB_DEVICE") (pin "GND") (pinfunction "GND_GND") (pintype "power_in"))
      (node (ref "USB_DEVICE") (pin "MT1") (pinfunction "SHIELD_MT1") (pintype "bidirectional"))
      (node (ref "USB_DEVICE") (pin "MT2") (pinfunction "SHIELD_MT2") (pintype "bidirectional"))
      (node (ref "USB_DEVICE") (pin "P$1") (pinfunction "SHIELD_P$1") (pintype "bidirectional"))
      (node (ref "USB_DEVICE") (pin "P$2") (pinfunction "SHIELD_P$2") (pintype "bidirectional"))
    )
    (net (code "88") (name "Net-(BOOTRST-Pad2)") (class "Default")
      (node (ref "BOOTRST") (pin "2") (pinfunction "2_2") (pintype "passive"))
      (node (ref "BOOTSEL") (pin "3") (pinfunction "2_3") (pintype "passive"))
      (node (ref "BOOTSEL") (pin "4") (pinfunction "2_4") (pintype "passive"))
      (node (ref "R3") (pin "1") (pinfunction "1_1") (pintype "passive"))
    )
    (net (code "89") (name "Net-(C24-Pad1)") (class "Default")
      (node (ref "C24") (pin "1") (pinfunction "1_1") (pintype "passive"))
      (node (ref "R5") (pin "1") (pinfunction "1_1") (pintype "passive"))
      (node (ref "X1") (pin "2") (pinfunction "2_2") (pintype "passive"))
    )
    (net (code "90") (name "Net-(IC2-GPIO25)") (class "Default")
      (node (ref "IC2") (pin "37") (pinfunction "GPIO25_37") (pintype "bidirectional"))
      (node (ref "R11") (pin "2") (pinfunction "2_2") (pintype "passive"))
    )
    (net (code "91") (name "Net-(IC2-QSPI_SCLK)") (class "Default")
      (node (ref "IC2") (pin "52") (pinfunction "QSPI_SCLK_52") (pintype "output"))
      (node (ref "U1") (pin "6") (pinfunction "SCK_6") (pintype "bidirectional"))
    )
    (net (code "92") (name "Net-(IC2-QSPI_SD0)") (class "Default")
      (node (ref "IC2") (pin "53") (pinfunction "QSPI_SD0_53") (pintype "bidirectional"))
      (node (ref "U1") (pin "5") (pinfunction "SI(D0)_5") (pintype "bidirectional"))
    )
    (net (code "93") (name "Net-(IC2-QSPI_SD1)") (class "Default")
      (node (ref "IC2") (pin "55") (pinfunction "QSPI_SD1_55") (pintype "bidirectional"))
      (node (ref "U1") (pin "2") (pinfunction "SO(D1)_2") (pintype "bidirectional"))
    )
    (net (code "94") (name "Net-(IC2-QSPI_SD2)") (class "Default")
      (node (ref "IC2") (pin "54") (pinfunction "QSPI_SD2_54") (pintype "bidirectional"))
      (node (ref "U1") (pin "3") (pinfunction "~{WP}(D2)_3") (pintype "bidirectional"))
    )
    (net (code "95") (name "Net-(IC2-QSPI_SD3)") (class "Default")
      (node (ref "IC2") (pin "51") (pinfunction "QSPI_SD3_51") (pintype "bidirectional"))
      (node (ref "U1") (pin "7") (pinfunction "~{HOLD}(D3)_7") (pintype "bidirectional"))
    )
    (net (code "96") (name "Net-(IC2-QSPI_SS)") (class "Default")
      (node (ref "IC2") (pin "56") (pinfunction "QSPI_SS_56") (pintype "bidirectional"))
      (node (ref "R13") (pin "1") (pinfunction "1_1") (pintype "passive"))
      (node (ref "R3") (pin "2") (pinfunction "2_2") (pintype "passive"))
      (node (ref "U1") (pin "1") (pinfunction "~{CS}_1") (pintype "bidirectional"))
    )
    (net (code "97") (name "Net-(IC2-SWCLK)") (class "Default")
      (node (ref "IC2") (pin "24") (pinfunction "SWCLK_24") (pintype "output"))
      (node (ref "SWD") (pin "3") (pinfunction "3_3") (pintype "passive"))
    )
    (net (code "98") (name "Net-(IC2-SWD)") (class "Default")
      (node (ref "IC2") (pin "25") (pinfunction "SWD_25") (pintype "bidirectional"))
      (node (ref "SWD") (pin "2") (pinfunction "2_2") (pintype "passive"))
    )
    (net (code "99") (name "Net-(IC2-USB_DM)") (class "Default")
      (node (ref "IC2") (pin "46") (pinfunction "USB_DM_46") (pintype "bidirectional"))
      (node (ref "R2") (pin "1") (pinfunction "1_1") (pintype "passive"))
    )
    (net (code "100") (name "Net-(IC2-USB_DP)") (class "Default")
      (node (ref "IC2") (pin "47") (pinfunction "USB_DP_47") (pintype "bidirectional"))
      (node (ref "R1") (pin "1") (pinfunction "1_1") (pintype "passive"))
    )
    (net (code "101") (name "Net-(IC2-XIN)") (class "Default")
      (node (ref "C23") (pin "1") (pinfunction "1_1") (pintype "passive"))
      (node (ref "IC2") (pin "20") (pinfunction "XIN_20") (pintype "input"))
      (node (ref "X1") (pin "1") (pinfunction "1_1") (pintype "passive"))
    )
    (net (code "102") (name "Net-(IC2-XOUT)") (class "Default")
      (node (ref "IC2") (pin "21") (pinfunction "XOUT_21") (pintype "passive"))
      (node (ref "R5") (pin "2") (pinfunction "2_2") (pintype "passive"))
    )
    (net (code "103") (name "Net-(IC3-1A1)") (class "Default")
      (node (ref "IC3") (pin "47") (pinfunction "1A1_47") (pintype "tri_state"))
      (node (ref "RN3") (pin "1") (pinfunction "1_1") (pintype "passive"))
    )
    (net (code "104") (name "Net-(IC3-1A2)") (class "Default")
      (node (ref "IC3") (pin "46") (pinfunction "1A2_46") (pintype "tri_state"))
      (node (ref "RN3") (pin "2") (pinfunction "1_2") (pintype "passive"))
    )
    (net (code "105") (name "Net-(IC3-1A3)") (class "Default")
      (node (ref "IC3") (pin "44") (pinfunction "1A3_44") (pintype "tri_state"))
      (node (ref "RN3") (pin "3") (pinfunction "1_3") (pintype "passive"))
    )
    (net (code "106") (name "Net-(IC3-1A4)") (class "Default")
      (node (ref "IC3") (pin "43") (pinfunction "1A4_43") (pintype "tri_state"))
      (node (ref "RN3") (pin "4") (pinfunction "1_4") (pintype "passive"))
    )
    (net (code "107") (name "Net-(IC3-1A5)") (class "Default")
      (node (ref "IC3") (pin "41") (pinfunction "1A5_41") (pintype "tri_state"))
      (node (ref "RN4") (pin "1") (pinfunction "1_1") (pintype "passive"))
    )
    (net (code "108") (name "Net-(IC3-1A6)") (class "Default")
      (node (ref "IC3") (pin "40") (pinfunction "1A6_40") (pintype "tri_state"))
      (node (ref "RN4") (pin "2") (pinfunction "1_2") (pintype "passive"))
    )
    (net (code "109") (name "Net-(IC3-1A7)") (class "Default")
      (node (ref "IC3") (pin "38") (pinfunction "1A7_38") (pintype "tri_state"))
      (node (ref "RN4") (pin "3") (pinfunction "1_3") (pintype "passive"))
    )
    (net (code "110") (name "Net-(IC3-1A8)") (class "Default")
      (node (ref "IC3") (pin "37") (pinfunction "1A8_37") (pintype "tri_state"))
      (node (ref "RN4") (pin "4") (pinfunction "1_4") (pintype "passive"))
    )
    (net (code "111") (name "Net-(IC3-2A1)") (class "Default")
      (node (ref "IC3") (pin "36") (pinfunction "2A1_36") (pintype "tri_state"))
      (node (ref "RN5") (pin "1") (pinfunction "1_1") (pintype "passive"))
    )
    (net (code "112") (name "Net-(IC3-2A2)") (class "Default")
      (node (ref "IC3") (pin "35") (pinfunction "2A2_35") (pintype "tri_state"))
      (node (ref "RN5") (pin "2") (pinfunction "1_2") (pintype "passive"))
    )
    (net (code "113") (name "Net-(IC3-2A3)") (class "Default")
      (node (ref "IC3") (pin "33") (pinfunction "2A3_33") (pintype "tri_state"))
      (node (ref "RN5") (pin "3") (pinfunction "1_3") (pintype "passive"))
    )
    (net (code "114") (name "Net-(IC3-2A4)") (class "Default")
      (node (ref "IC3") (pin "32") (pinfunction "2A4_32") (pintype "tri_state"))
      (node (ref "RN5") (pin "4") (pinfunction "1_4") (pintype "passive"))
    )
    (net (code "115") (name "Net-(IC3-2B2)") (class "Default")
      (node (ref "IC3") (pin "14") (pinfunction "2B2_14") (pintype "tri_state"))
      (node (ref "IC3") (pin "16") (pinfunction "2B3_16") (pintype "tri_state"))
      (node (ref "IC3") (pin "17") (pinfunction "2B4_17") (pintype "tri_state"))
      (node (ref "IC3") (pin "19") (pinfunction "2B5_19") (pintype "tri_state"))
      (node (ref "IC3") (pin "20") (pinfunction "2B6_20") (pintype "tri_state"))
      (node (ref "IC3") (pin "22") (pinfunction "2B7_22") (pintype "tri_state"))
      (node (ref "IC3") (pin "23") (pinfunction "2B8_23") (pintype "tri_state"))
      (node (ref "R10") (pin "2") (pinfunction "2_2") (pintype "passive"))
    )
    (net (code "116") (name "Net-(IC4-1A1)") (class "Default")
      (node (ref "IC4") (pin "47") (pinfunction "1A1_47") (pintype "tri_state"))
      (node (ref "RN6") (pin "1") (pinfunction "1_1") (pintype "passive"))
    )
    (net (code "117") (name "Net-(IC4-1A2)") (class "Default")
      (node (ref "IC4") (pin "46") (pinfunction "1A2_46") (pintype "tri_state"))
      (node (ref "RN6") (pin "2") (pinfunction "1_2") (pintype "passive"))
    )
    (net (code "118") (name "Net-(IC4-1A3)") (class "Default")
      (node (ref "IC4") (pin "44") (pinfunction "1A3_44") (pintype "tri_state"))
      (node (ref "RN6") (pin "3") (pinfunction "1_3") (pintype "passive"))
    )
    (net (code "119") (name "Net-(IC4-1A4)") (class "Default")
      (node (ref "IC4") (pin "43") (pinfunction "1A4_43") (pintype "tri_state"))
      (node (ref "RN6") (pin "4") (pinfunction "1_4") (pintype "passive"))
    )
    (net (code "120") (name "Net-(IC4-1A5)") (class "Default")
      (node (ref "IC4") (pin "41") (pinfunction "1A5_41") (pintype "tri_state"))
      (node (ref "RN7") (pin "1") (pinfunction "1_1") (pintype "passive"))
    )
    (net (code "121") (name "Net-(IC4-1A6)") (class "Default")
      (node (ref "IC4") (pin "40") (pinfunction "1A6_40") (pintype "tri_state"))
      (node (ref "RN7") (pin "2") (pinfunction "1_2") (pintype "passive"))
    )
    (net (code "122") (name "Net-(IC4-1A7)") (class "Default")
      (node (ref "IC4") (pin "38") (pinfunction "1A7_38") (pintype "tri_state"))
      (node (ref "RN7") (pin "3") (pinfunction "1_3") (pintype "passive"))
    )
    (net (code "123") (name "Net-(IC4-1A8)") (class "Default")
      (node (ref "IC4") (pin "37") (pinfunction "1A8_37") (pintype "tri_state"))
      (node (ref "RN7") (pin "4") (pinfunction "1_4") (pintype "passive"))
    )
    (net (code "124") (name "Net-(IC4-2A1)") (class "Default")
      (node (ref "IC4") (pin "36") (pinfunction "2A1_36") (pintype "tri_state"))
      (node (ref "RN8") (pin "1") (pinfunction "1_1") (pintype "passive"))
    )
    (net (code "125") (name "Net-(IC4-2A2)") (class "Default")
      (node (ref "IC4") (pin "35") (pinfunction "2A2_35") (pintype "tri_state"))
      (node (ref "RN8") (pin "2") (pinfunction "1_2") (pintype "passive"))
    )
    (net (code "126") (name "Net-(IC4-2A3)") (class "Default")
      (node (ref "IC4") (pin "33") (pinfunction "2A3_33") (pintype "tri_state"))
      (node (ref "RN8") (pin "3") (pinfunction "1_3") (pintype "passive"))
    )
    (net (code "127") (name "Net-(IC4-2A4)") (class "Default")
      (node (ref "IC4") (pin "32") (pinfunction "2A4_32") (pintype "tri_state"))
      (node (ref "RN8") (pin "4") (pinfunction "1_4") (pintype "passive"))
    )
    (net (code "128") (name "Net-(IC4-2A5)") (class "Default")
      (node (ref "IC4") (pin "30") (pinfunction "2A5_30") (pintype "tri_state"))
      (node (ref "RN9") (pin "1") (pinfunction "1_1") (pintype "passive"))
    )
    (net (code "129") (name "Net-(IC4-2A6)") (class "Default")
      (node (ref "IC4") (pin "29") (pinfunction "2A6_29") (pintype "tri_state"))
      (node (ref "RN9") (pin "2") (pinfunction "1_2") (pintype "passive"))
    )
    (net (code "130") (name "Net-(IC4-2A7)") (class "Default")
      (node (ref "IC4") (pin "27") (pinfunction "2A7_27") (pintype "tri_state"))
      (node (ref "RN9") (pin "3") (pinfunction "1_3") (pintype "passive"))
    )
    (net (code "131") (name "Net-(IC4-2A8)") (class "Default")
      (node (ref "IC4") (pin "26") (pinfunction "2A8_26") (pintype "tri_state"))
      (node (ref "RN9") (pin "4") (pinfunction "1_4") (pintype "passive"))
    )
    (net (code "132") (name "Net-(LED1-PadA)") (class "Default")
      (node (ref "LED1") (pin "A") (pinfunction "A_A") (pintype "passive"))
      (node (ref "R11") (pin "1") (pinfunction "1_1") (pintype "passive"))
    )
    (net (code "133") (name "Net-(MICROSD-CD{slash}DAT3)") (class "Default")
      (node (ref "MICROSD") (pin "2") (pinfunction "CD/DAT3_2") (pintype "bidirectional"))
      (node (ref "RN10") (pin "8") (pinfunction "2_8") (pintype "passive"))
    )
    (net (code "134") (name "Net-(MICROSD-CLK)") (class "Default")
      (node (ref "MICROSD") (pin "5") (pinfunction "CLK_5") (pintype "bidirectional"))
      (node (ref "RN10") (pin "5") (pinfunction "2_5") (pintype "passive"))
    )
    (net (code "135") (name "Net-(MICROSD-CMD)") (class "Default")
      (node (ref "MICROSD") (pin "3") (pinfunction "CMD_3") (pintype "bidirectional"))
      (node (ref "RN10") (pin "6") (pinfunction "2_6") (pintype "passive"))
    )
    (net (code "136") (name "Net-(MICROSD-DAT0)") (class "Default")
      (node (ref "MICROSD") (pin "7") (pinfunction "DAT0_7") (pintype "bidirectional"))
      (node (ref "R4") (pin "1") (pinfunction "1_1") (pintype "passive"))
      (node (ref "RN10") (pin "7") (pinfunction "2_7") (pintype "passive"))
    )
    (net (code "137") (name "Net-(Q1-B)") (class "Default")
      (node (ref "Q1") (pin "1") (pinfunction "B_1") (pintype "passive"))
      (node (ref "R7") (pin "1") (pinfunction "1_1") (pintype "passive"))
    )
    (net (code "138") (name "Net-(Q2-B)") (class "Default")
      (node (ref "Q2") (pin "1") (pinfunction "B_1") (pintype "passive"))
      (node (ref "R9") (pin "1") (pinfunction "1_1") (pintype "passive"))
    )
    (net (code "139") (name "Net-(R1-Pad2)") (class "Default")
      (node (ref "R1") (pin "2") (pinfunction "2_2") (pintype "passive"))
      (node (ref "USB_DEVICE") (pin "D+") (pinfunction "D+_D+") (pintype "bidirectional"))
    )
    (net (code "140") (name "Net-(R2-Pad2)") (class "Default")
      (node (ref "R2") (pin "2") (pinfunction "2_2") (pintype "passive"))
      (node (ref "USB_DEVICE") (pin "D-") (pinfunction "D-_D-") (pintype "bidirectional"))
    )
    (net (code "141") (name "VCCINT") (class "Default")
      (node (ref "C15") (pin "1") (pinfunction "1_1") (pintype "passive"))
      (node (ref "C16") (pin "1") (pinfunction "1_1") (pintype "passive"))
      (node (ref "C22") (pin "1") (pinfunction "1_1") (pintype "passive"))
      (node (ref "IC2") (pin "23") (pinfunction "DVDD0_23") (pintype "power_in"))
      (node (ref "IC2") (pin "45") (pinfunction "VREG_OUT_45") (pintype "power_in"))
      (node (ref "IC2") (pin "50") (pinfunction "DVDD1_50") (pintype "power_in"))
    )
    (net (code "142") (name "V_USB") (class "Default")
      (node (ref "D2") (pin "1") (pinfunction "A_1") (pintype "passive"))
      (node (ref "USB_DEVICE") (pin "VBUS") (pinfunction "VBUS_VBUS") (pintype "power_in"))
    )
    (net (code "143") (name "unconnected-(IC3-2A5-Pad30)") (class "Default")
      (node (ref "IC3") (pin "30") (pinfunction "2A5_30") (pintype "tri_state"))
    )
    (net (code "144") (name "unconnected-(IC3-2A6-Pad29)") (class "Default")
      (node (ref "IC3") (pin "29") (pinfunction "2A6_29") (pintype "tri_state"))
    )
    (net (code "145") (name "unconnected-(IC3-2A7-Pad27)") (class "Default")
      (node (ref "IC3") (pin "27") (pinfunction "2A7_27") (pintype "tri_state"))
    )
    (net (code "146") (name "unconnected-(IC3-2A8-Pad26)") (class "Default")
      (node (ref "IC3") (pin "26") (pinfunction "2A8_26") (pintype "tri_state"))
    )
    (net (code "147") (name "unconnected-(J1-PadC2)") (class "Default")
      (node (ref "J1") (pin "C2") (pinfunction "C2_C2") (pintype "passive"))
    )
    (net (code "148") (name "unconnected-(J1-PadC5)") (class "Default")
      (node (ref "J1") (pin "C5") (pinfunction "C5_C5") (pintype "passive"))
    )
    (net (code "149") (name "unconnected-(J1-PadC7)") (class "Default")
      (node (ref "J1") (pin "C7") (pinfunction "C7_C7") (pintype "passive"))
    )
    (net (code "150") (name "unconnected-(J1-PadC8)") (class "Default")
      (node (ref "J1") (pin "C8") (pinfunction "C8_C8") (pintype "passive"))
    )
    (net (code "151") (name "unconnected-(J1-PadC9)") (class "Default")
      (node (ref "J1") (pin "C9") (pinfunction "C9_C9") (pintype "passive"))
    )
    (net (code "152") (name "unconnected-(J1-PadC10)") (class "Default")
      (node (ref "J1") (pin "C10") (pinfunction "C10_C10") (pintype "passive"))
    )
    (net (code "153") (name "unconnected-(J1-PadC11)") (class "Default")
      (node (ref "J1") (pin "C11") (pinfunction "C11_C11") (pintype "passive"))
    )
    (net (code "154") (name "unconnected-(J1-PadC18)") (class "Default")
      (node (ref "J1") (pin "C18") (pinfunction "C18_C18") (pintype "passive"))
    )
    (net (code "155") (name "unconnected-(J1-PadC21)") (class "Default")
      (node (ref "J1") (pin "C21") (pinfunction "C21_C21") (pintype "passive"))
    )
    (net (code "156") (name "unconnected-(J1-PadC29)") (class "Default")
      (node (ref "J1") (pin "C29") (pinfunction "C29_C29") (pintype "passive"))
    )
    (net (code "157") (name "unconnected-(J1-PadC31)") (class "Default")
      (node (ref "J1") (pin "C31") (pinfunction "C31_C31") (pintype "passive"))
    )
    (net (code "158") (name "unconnected-(J1-PadC32)") (class "Default")
      (node (ref "J1") (pin "C32") (pinfunction "C32_C32") (pintype "passive"))
    )
    (net (code "159") (name "unconnected-(MICROSD-DAT1-Pad8)") (class "Default")
      (node (ref "MICROSD") (pin "8") (pinfunction "DAT1_8") (pintype "bidirectional"))
    )
    (net (code "160") (name "unconnected-(MICROSD-DAT2-Pad1)") (class "Default")
      (node (ref "MICROSD") (pin "1") (pinfunction "DAT2_1") (pintype "bidirectional"))
    )
    (net (code "161") (name "unconnected-(MICROSD-DET-PadG4)") (class "Default")
      (node (ref "MICROSD") (pin "G4") (pinfunction "DET_G4") (pintype "bidirectional"))
    )
    (net (code "162") (name "unconnected-(MICROSD-POL-PadG3)") (class "Default")
      (node (ref "MICROSD") (pin "G3") (pinfunction "POL_G3") (pintype "bidirectional"))
    )
    (net (code "163") (name "unconnected-(RN5B-2-Pad7)") (class "Default")
      (node (ref "RN5") (pin "7") (pinfunction "2_7") (pintype "passive"))
    )
    (net (code "164") (name "unconnected-(RN5C-2-Pad6)") (class "Default")
      (node (ref "RN5") (pin "6") (pinfunction "2_6") (pintype "passive"))
    )
    (net (code "165") (name "unconnected-(RN5D-2-Pad5)") (class "Default")
      (node (ref "RN5") (pin "5") (pinfunction "2_5") (pintype "passive"))
    )
    (net (code "166") (name "unconnected-(RN9C-2-Pad6)") (class "Default")
      (node (ref "RN9") (pin "6") (pinfunction "2_6") (pintype "passive"))
    )
    (net (code "167") (name "unconnected-(RN9D-2-Pad5)") (class "Default")
      (node (ref "RN9") (pin "5") (pinfunction "2_5") (pintype "passive"))
    )
    (net (code "168") (name "unconnected-(U2-BP-Pad4)") (class "Default")
      (node (ref "U2") (pin "4") (pinfunction "BP_4") (pintype "input"))
    )
    (net (code "169") (name "unconnected-(USB_DEVICE-PadID)") (class "Default")
      (node (ref "USB_DEVICE") (pin "ID") (pinfunction "ID_ID") (pintype "bidirectional"))
    )
  )
)
